# OLED_0_96.net
KiCad netlist of a schematic drawn in Altium Designer
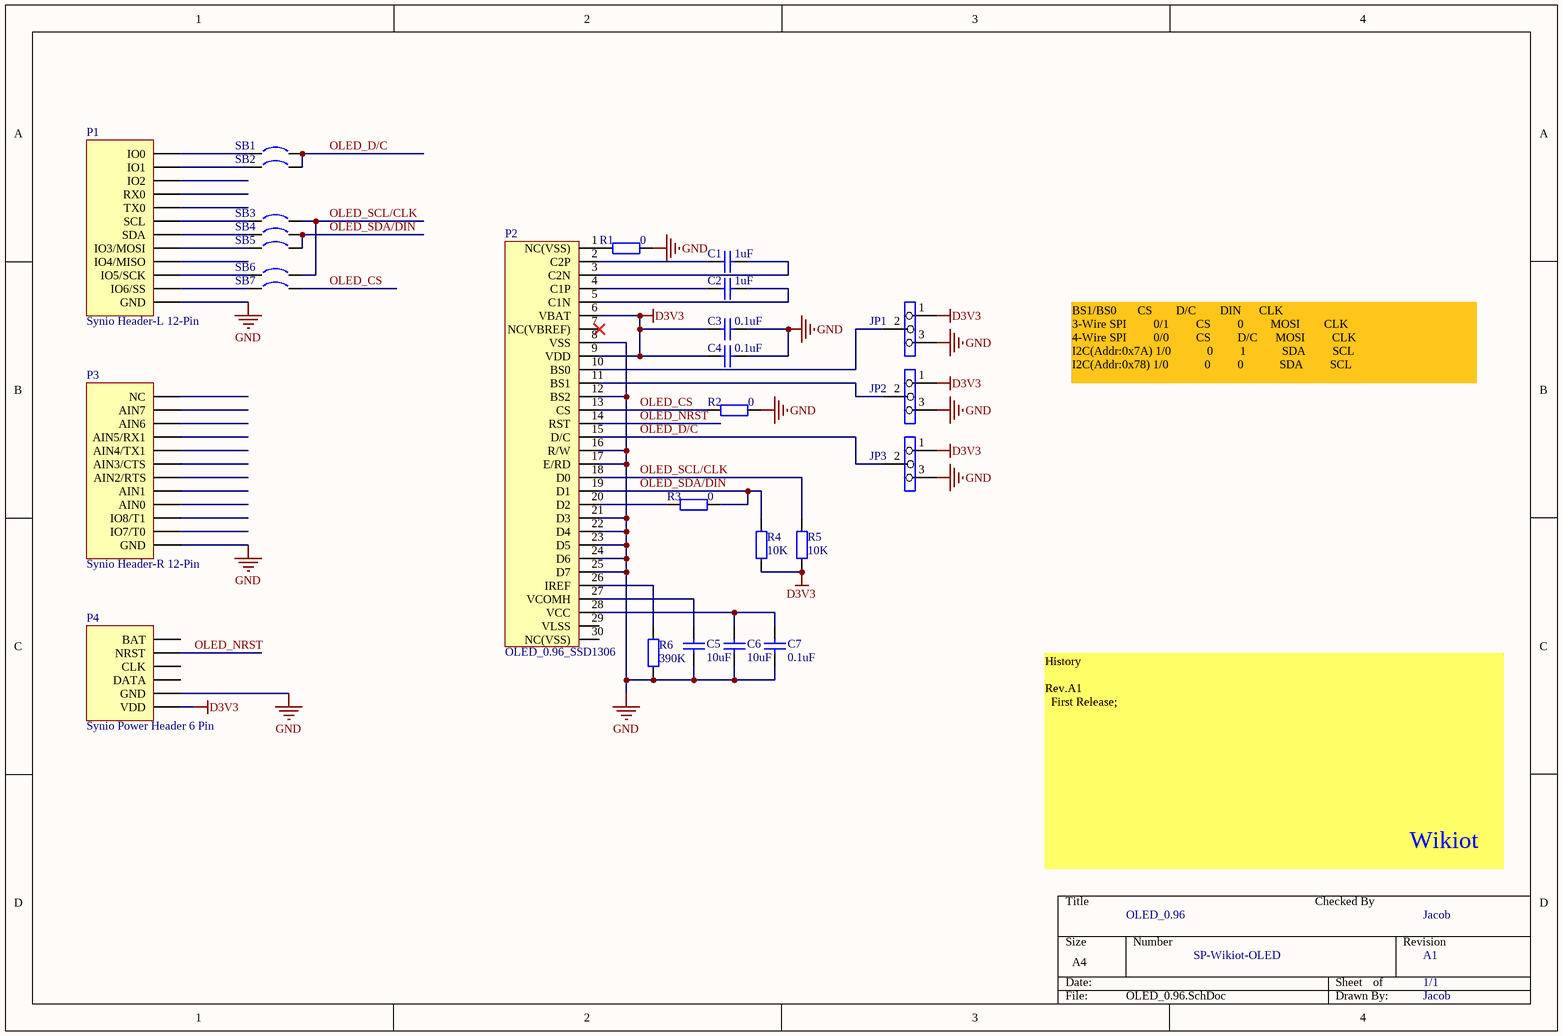
[diagram p0: OLED_0.96.SchDoc]

(export (version "E")
  (design (tool "Eeschema 10.0.6"))
  (components
    (comp (ref "*") (value "LOGO") (footprint "Logo") (libsource (lib "Misc") (part "LOGO")))
    (comp (ref "C1")
      (value "1uF")
      (footprint "0603C")
      (description "Capacitor")
      (libsource (lib "Misc") (part "Cap"))
    )
    (comp (ref "C2")
      (value "1uF")
      (footprint "0603C")
      (description "Capacitor")
      (libsource (lib "Misc") (part "Cap"))
    )
    (comp (ref "C3")
      (value "0.1uF")
      (footprint "0603C")
      (description "Capacitor")
      (libsource (lib "Misc") (part "Cap"))
    )
    (comp (ref "C4")
      (value "0.1uF")
      (footprint "0603C")
      (description "Capacitor")
      (libsource (lib "Misc") (part "Cap"))
    )
    (comp (ref "C5")
      (value "10uF")
      (footprint "0603C")
      (description "Capacitor")
      (libsource (lib "Misc") (part "Cap"))
    )
    (comp (ref "C6")
      (value "10uF")
      (footprint "0603C")
      (description "Capacitor")
      (libsource (lib "Misc") (part "Cap"))
    )
    (comp (ref "C7")
      (value "0.1uF")
      (footprint "0603C")
      (description "Capacitor")
      (libsource (lib "Misc") (part "Cap"))
    )
    (comp (ref "JP1") (value "JP3") (footprint "JUMPER3_SMD") (libsource (lib "Connector") (part "JP3")))
    (comp (ref "JP2") (value "JP3") (footprint "JUMPER3_SMD") (libsource (lib "Connector") (part "JP3")))
    (comp (ref "JP3") (value "JP3") (footprint "JUMPER3_SMD") (libsource (lib "Connector") (part "JP3")))
    (comp (ref "P1")
      (value "Synio Header-L 12-Pin")
      (footprint "HDR1X12/2.54MM")
      (description "Synio Header-L, 12-Pin")
      (fields (field (name "PUBLISHER") "Altium Limited"))
      (libsource (lib "Connector") (part "Synio Header-L 12-Pin"))
    )
    (comp (ref "P2")
      (value "OLED_0.96_SSD1306")
      (footprint "OLED_0.96_SSD1306")
      (libsource (lib "LCD") (part "OLED_0.96_SSD1306"))
    )
    (comp (ref "P3")
      (value "Synio Header-R 12-Pin")
      (footprint "HDR1X12/2.54MM")
      (description "Synio Header-R, 12-Pin")
      (fields (field (name "PUBLISHER") "Altium Limited"))
      (libsource (lib "Connector") (part "Synio Header-R 12-Pin"))
    )
    (comp (ref "P4")
      (value "Synio Power Header 6 Pin")
      (footprint "HDR1X6/2.54MM")
      (libsource (lib "Connector") (part "Synio Power Header 6 Pin"))
    )
    (comp (ref "R1")
      (value "0")
      (footprint "0603R")
      (description "Resistor")
      (fields (field (name "PUBLISHER") "Altium Limited"))
      (libsource (lib "Misc") (part "Res"))
    )
    (comp (ref "R2")
      (value "0")
      (footprint "0603R")
      (description "Resistor")
      (fields (field (name "PUBLISHER") "Altium Limited"))
      (libsource (lib "Misc") (part "Res"))
    )
    (comp (ref "R3")
      (value "0")
      (footprint "0603R")
      (description "Resistor")
      (fields (field (name "PUBLISHER") "Altium Limited"))
      (libsource (lib "Misc") (part "Res"))
    )
    (comp (ref "R4")
      (value "10K")
      (footprint "0603R")
      (description "Resistor")
      (fields (field (name "PUBLISHER") "Altium Limited"))
      (libsource (lib "") (part "Res_1"))
    )
    (comp (ref "R5")
      (value "10K")
      (footprint "0603R")
      (description "Resistor")
      (fields (field (name "PUBLISHER") "Altium Limited"))
      (libsource (lib "") (part "Res_1"))
    )
    (comp (ref "R6")
      (value "390K")
      (footprint "0603R")
      (description "Resistor")
      (fields (field (name "PUBLISHER") "Altium Limited"))
      (libsource (lib "") (part "Res_1"))
    )
    (comp (ref "SB1")
      (value "Circuit Breaker")
      (footprint "JP2_SMD")
      (fields (field (name "PUBLISHER") "Altium Limited"))
      (libsource (lib "Misc") (part "Circuit Breaker"))
    )
    (comp (ref "SB2")
      (value "Circuit Breaker")
      (footprint "JP2_SMD")
      (fields (field (name "PUBLISHER") "Altium Limited"))
      (libsource (lib "Misc") (part "Circuit Breaker"))
    )
    (comp (ref "SB3")
      (value "Circuit Breaker")
      (footprint "JP2_SMD")
      (fields (field (name "PUBLISHER") "Altium Limited"))
      (libsource (lib "Misc") (part "Circuit Breaker"))
    )
    (comp (ref "SB4")
      (value "Circuit Breaker")
      (footprint "JP2_SMD")
      (fields (field (name "PUBLISHER") "Altium Limited"))
      (libsource (lib "Misc") (part "Circuit Breaker"))
    )
    (comp (ref "SB5")
      (value "Circuit Breaker")
      (footprint "JP2_SMD")
      (fields (field (name "PUBLISHER") "Altium Limited"))
      (libsource (lib "Misc") (part "Circuit Breaker"))
    )
    (comp (ref "SB6")
      (value "Circuit Breaker")
      (footprint "JP2_SMD")
      (fields (field (name "PUBLISHER") "Altium Limited"))
      (libsource (lib "Misc") (part "Circuit Breaker"))
    )
    (comp (ref "SB7")
      (value "Circuit Breaker")
      (footprint "JP2_SMD")
      (fields (field (name "PUBLISHER") "Altium Limited"))
      (libsource (lib "Misc") (part "Circuit Breaker"))
    )
  )
  (nets
    (net (code "1") (name "/OLED_CS") (class "Default")
      (node (ref "P2") (pin "13") (pinfunction "CS_13") (pintype "passive"))
      (node (ref "R2") (pin "1") (pinfunction "1_1") (pintype "passive"))
      (node (ref "SB7") (pin "2") (pinfunction "2_2") (pintype "passive"))
    )
    (net (code "2") (name "/OLED_D{slash}C") (class "Default")
      (node (ref "JP3") (pin "2") (pintype "passive"))
      (node (ref "P2") (pin "15") (pinfunction "D/C_15") (pintype "passive"))
      (node (ref "SB1") (pin "2") (pinfunction "2_2") (pintype "passive"))
      (node (ref "SB2") (pin "2") (pinfunction "2_2") (pintype "passive"))
    )
    (net (code "3") (name "/OLED_NRST") (class "Default")
      (node (ref "P2") (pin "14") (pinfunction "RST_14") (pintype "passive"))
      (node (ref "P4") (pin "5") (pinfunction "NRST_5") (pintype "passive"))
    )
    (net (code "4") (name "/OLED_SCL{slash}CLK") (class "Default")
      (node (ref "P2") (pin "18") (pinfunction "D0_18") (pintype "passive"))
      (node (ref "R5") (pin "2") (pinfunction "2_2") (pintype "passive"))
      (node (ref "SB3") (pin "2") (pinfunction "2_2") (pintype "passive"))
      (node (ref "SB6") (pin "2") (pinfunction "2_2") (pintype "passive"))
    )
    (net (code "5") (name "/OLED_SDA{slash}DIN") (class "Default")
      (node (ref "P2") (pin "19") (pinfunction "D1_19") (pintype "passive"))
      (node (ref "R3") (pin "2") (pinfunction "2_2") (pintype "passive"))
      (node (ref "R4") (pin "2") (pinfunction "2_2") (pintype "passive"))
      (node (ref "SB4") (pin "2") (pinfunction "2_2") (pintype "passive"))
      (node (ref "SB5") (pin "2") (pinfunction "2_2") (pintype "passive"))
    )
    (net (code "6") (name "D3V3") (class "Default")
      (node (ref "C3") (pin "1") (pinfunction "1_1") (pintype "passive"))
      (node (ref "C4") (pin "2") (pinfunction "2_2") (pintype "passive"))
      (node (ref "JP1") (pin "1") (pintype "passive"))
      (node (ref "JP2") (pin "1") (pintype "passive"))
      (node (ref "JP3") (pin "1") (pintype "passive"))
      (node (ref "P2") (pin "6") (pinfunction "VBAT_6") (pintype "passive"))
      (node (ref "P2") (pin "9") (pinfunction "VDD_9") (pintype "passive"))
      (node (ref "P4") (pin "1") (pinfunction "VDD_1") (pintype "passive"))
      (node (ref "R4") (pin "1") (pinfunction "1_1") (pintype "passive"))
      (node (ref "R5") (pin "1") (pinfunction "1_1") (pintype "passive"))
    )
    (net (code "7") (name "GND") (class "Default")
      (node (ref "C3") (pin "2") (pinfunction "2_2") (pintype "passive"))
      (node (ref "C4") (pin "1") (pinfunction "1_1") (pintype "passive"))
      (node (ref "C5") (pin "2") (pinfunction "2_2") (pintype "passive"))
      (node (ref "C6") (pin "2") (pinfunction "2_2") (pintype "passive"))
      (node (ref "C7") (pin "2") (pinfunction "2_2") (pintype "passive"))
      (node (ref "JP1") (pin "3") (pintype "passive"))
      (node (ref "JP2") (pin "3") (pintype "passive"))
      (node (ref "JP3") (pin "3") (pintype "passive"))
      (node (ref "P1") (pin "1") (pinfunction "GND_1") (pintype "passive"))
      (node (ref "P2") (pin "12") (pinfunction "BS2_12") (pintype "passive"))
      (node (ref "P2") (pin "16") (pinfunction "R/W_16") (pintype "passive"))
      (node (ref "P2") (pin "17") (pinfunction "E/RD_17") (pintype "passive"))
      (node (ref "P2") (pin "21") (pinfunction "D3_21") (pintype "passive"))
      (node (ref "P2") (pin "22") (pinfunction "D4_22") (pintype "passive"))
      (node (ref "P2") (pin "23") (pinfunction "D5_23") (pintype "passive"))
      (node (ref "P2") (pin "24") (pinfunction "D6_24") (pintype "passive"))
      (node (ref "P2") (pin "25") (pinfunction "D7_25") (pintype "passive"))
      (node (ref "P2") (pin "8") (pinfunction "VSS_8") (pintype "passive"))
      (node (ref "P3") (pin "1") (pinfunction "GND_1") (pintype "passive"))
      (node (ref "P4") (pin "2") (pinfunction "GND_2") (pintype "passive"))
      (node (ref "R1") (pin "2") (pinfunction "2_2") (pintype "passive"))
      (node (ref "R2") (pin "2") (pinfunction "2_2") (pintype "passive"))
      (node (ref "R6") (pin "1") (pinfunction "1_1") (pintype "passive"))
    )
    (net (code "8") (name "Net-(P1-IO0)") (class "Default")
      (node (ref "P1") (pin "12") (pinfunction "IO0_12") (pintype "passive"))
      (node (ref "SB1") (pin "1") (pinfunction "1_1") (pintype "passive"))
    )
    (net (code "9") (name "Net-(P1-IO1)") (class "Default")
      (node (ref "P1") (pin "11") (pinfunction "IO1_11") (pintype "passive"))
      (node (ref "SB2") (pin "1") (pinfunction "1_1") (pintype "passive"))
    )
    (net (code "10") (name "Net-(P1-IO3{slash}MOSI)") (class "Default")
      (node (ref "P1") (pin "5") (pinfunction "IO3/MOSI_5") (pintype "passive"))
      (node (ref "SB5") (pin "1") (pinfunction "1_1") (pintype "passive"))
    )
    (net (code "11") (name "Net-(P1-IO5{slash}SCK)") (class "Default")
      (node (ref "P1") (pin "3") (pinfunction "IO5/SCK_3") (pintype "passive"))
      (node (ref "SB6") (pin "1") (pinfunction "1_1") (pintype "passive"))
    )
    (net (code "12") (name "Net-(P1-IO6{slash}SS)") (class "Default")
      (node (ref "P1") (pin "2") (pinfunction "IO6/SS_2") (pintype "passive"))
      (node (ref "SB7") (pin "1") (pinfunction "1_1") (pintype "passive"))
    )
    (net (code "13") (name "Net-(P1-SCL)") (class "Default")
      (node (ref "P1") (pin "7") (pinfunction "SCL_7") (pintype "passive"))
      (node (ref "SB3") (pin "1") (pinfunction "1_1") (pintype "passive"))
    )
    (net (code "14") (name "Net-(P1-SDA)") (class "Default")
      (node (ref "P1") (pin "6") (pinfunction "SDA_6") (pintype "passive"))
      (node (ref "SB4") (pin "1") (pinfunction "1_1") (pintype "passive"))
    )
    (net (code "15") (name "Net-(P2-BS0)") (class "Default")
      (node (ref "JP1") (pin "2") (pintype "passive"))
      (node (ref "P2") (pin "10") (pinfunction "BS0_10") (pintype "passive"))
    )
    (net (code "16") (name "Net-(P2-BS1)") (class "Default")
      (node (ref "JP2") (pin "2") (pintype "passive"))
      (node (ref "P2") (pin "11") (pinfunction "BS1_11") (pintype "passive"))
    )
    (net (code "17") (name "Net-(P2-C1N)") (class "Default")
      (node (ref "C2") (pin "2") (pinfunction "2_2") (pintype "passive"))
      (node (ref "P2") (pin "5") (pinfunction "C1N_5") (pintype "passive"))
    )
    (net (code "18") (name "Net-(P2-C1P)") (class "Default")
      (node (ref "C2") (pin "1") (pinfunction "1_1") (pintype "passive"))
      (node (ref "P2") (pin "4") (pinfunction "C1P_4") (pintype "passive"))
    )
    (net (code "19") (name "Net-(P2-C2N)") (class "Default")
      (node (ref "C1") (pin "2") (pinfunction "2_2") (pintype "passive"))
      (node (ref "P2") (pin "3") (pinfunction "C2N_3") (pintype "passive"))
    )
    (net (code "20") (name "Net-(P2-C2P)") (class "Default")
      (node (ref "C1") (pin "1") (pinfunction "1_1") (pintype "passive"))
      (node (ref "P2") (pin "2") (pinfunction "C2P_2") (pintype "passive"))
    )
    (net (code "21") (name "Net-(P2-D2)") (class "Default")
      (node (ref "P2") (pin "20") (pinfunction "D2_20") (pintype "passive"))
      (node (ref "R3") (pin "1") (pinfunction "1_1") (pintype "passive"))
    )
    (net (code "22") (name "Net-(P2-IREF)") (class "Default")
      (node (ref "P2") (pin "26") (pinfunction "IREF_26") (pintype "passive"))
      (node (ref "R6") (pin "2") (pinfunction "2_2") (pintype "passive"))
    )
    (net (code "23") (name "Net-(P2-NC(VSS)-Pad1)") (class "Default")
      (node (ref "P2") (pin "1") (pinfunction "NC(VSS)_1") (pintype "passive"))
      (node (ref "R1") (pin "1") (pinfunction "1_1") (pintype "passive"))
    )
    (net (code "24") (name "Net-(P2-VCC)") (class "Default")
      (node (ref "C6") (pin "1") (pinfunction "1_1") (pintype "passive"))
      (node (ref "C7") (pin "1") (pinfunction "1_1") (pintype "passive"))
      (node (ref "P2") (pin "28") (pinfunction "VCC_28") (pintype "passive"))
    )
    (net (code "25") (name "Net-(P2-VCOMH)") (class "Default")
      (node (ref "C5") (pin "1") (pinfunction "1_1") (pintype "passive"))
      (node (ref "P2") (pin "27") (pinfunction "VCOMH_27") (pintype "passive"))
    )
    (net (code "26") (name "unconnected-(P1-IO2-Pad10)") (class "Default")
      (node (ref "P1") (pin "10") (pinfunction "IO2_10") (pintype "passive"))
    )
    (net (code "27") (name "unconnected-(P1-IO4{slash}MISO-Pad4)") (class "Default")
      (node (ref "P1") (pin "4") (pinfunction "IO4/MISO_4") (pintype "passive"))
    )
    (net (code "28") (name "unconnected-(P1-RX0-Pad9)") (class "Default")
      (node (ref "P1") (pin "9") (pinfunction "RX0_9") (pintype "passive"))
    )
    (net (code "29") (name "unconnected-(P1-TX0-Pad8)") (class "Default")
      (node (ref "P1") (pin "8") (pinfunction "TX0_8") (pintype "passive"))
    )
    (net (code "30") (name "unconnected-(P2-NC(VBREF)-Pad7)") (class "Default")
      (node (ref "P2") (pin "7") (pinfunction "NC(VBREF)_7") (pintype "passive+no_connect"))
    )
    (net (code "31") (name "unconnected-(P2-NC(VSS)-Pad30)") (class "Default")
      (node (ref "P2") (pin "30") (pinfunction "NC(VSS)_30") (pintype "passive"))
    )
    (net (code "32") (name "unconnected-(P2-VLSS-Pad29)") (class "Default")
      (node (ref "P2") (pin "29") (pinfunction "VLSS_29") (pintype "passive"))
    )
    (net (code "33") (name "unconnected-(P3-AIN0-Pad4)") (class "Default")
      (node (ref "P3") (pin "4") (pinfunction "AIN0_4") (pintype "passive"))
    )
    (net (code "34") (name "unconnected-(P3-AIN1-Pad5)") (class "Default")
      (node (ref "P3") (pin "5") (pinfunction "AIN1_5") (pintype "passive"))
    )
    (net (code "35") (name "unconnected-(P3-AIN2{slash}RTS-Pad6)") (class "Default")
      (node (ref "P3") (pin "6") (pinfunction "AIN2/RTS_6") (pintype "passive"))
    )
    (net (code "36") (name "unconnected-(P3-AIN3{slash}CTS-Pad7)") (class "Default")
      (node (ref "P3") (pin "7") (pinfunction "AIN3/CTS_7") (pintype "passive"))
    )
    (net (code "37") (name "unconnected-(P3-AIN4{slash}TX1-Pad8)") (class "Default")
      (node (ref "P3") (pin "8") (pinfunction "AIN4/TX1_8") (pintype "passive"))
    )
    (net (code "38") (name "unconnected-(P3-AIN5{slash}RX1-Pad9)") (class "Default")
      (node (ref "P3") (pin "9") (pinfunction "AIN5/RX1_9") (pintype "passive"))
    )
    (net (code "39") (name "unconnected-(P3-AIN6-Pad10)") (class "Default")
      (node (ref "P3") (pin "10") (pinfunction "AIN6_10") (pintype "passive"))
    )
    (net (code "40") (name "unconnected-(P3-AIN7-Pad11)") (class "Default")
      (node (ref "P3") (pin "11") (pinfunction "AIN7_11") (pintype "passive"))
    )
    (net (code "41") (name "unconnected-(P3-IO7{slash}T0-Pad2)") (class "Default")
      (node (ref "P3") (pin "2") (pinfunction "IO7/T0_2") (pintype "passive"))
    )
    (net (code "42") (name "unconnected-(P3-IO8{slash}T1-Pad3)") (class "Default")
      (node (ref "P3") (pin "3") (pinfunction "IO8/T1_3") (pintype "passive"))
    )
    (net (code "43") (name "unconnected-(P3-NC-Pad12)") (class "Default")
      (node (ref "P3") (pin "12") (pinfunction "NC_12") (pintype "passive"))
    )
    (net (code "44") (name "unconnected-(P4-BAT-Pad6)") (class "Default")
      (node (ref "P4") (pin "6") (pinfunction "BAT_6") (pintype "passive"))
    )
    (net (code "45") (name "unconnected-(P4-CLK-Pad4)") (class "Default")
      (node (ref "P4") (pin "4") (pinfunction "CLK_4") (pintype "passive"))
    )
    (net (code "46") (name "unconnected-(P4-DATA-Pad3)") (class "Default")
      (node (ref "P4") (pin "3") (pinfunction "DATA_3") (pintype "passive"))
    )
  )
)
